# seccionamento.net
KiCad netlist of a schematic drawn in Altium Designer
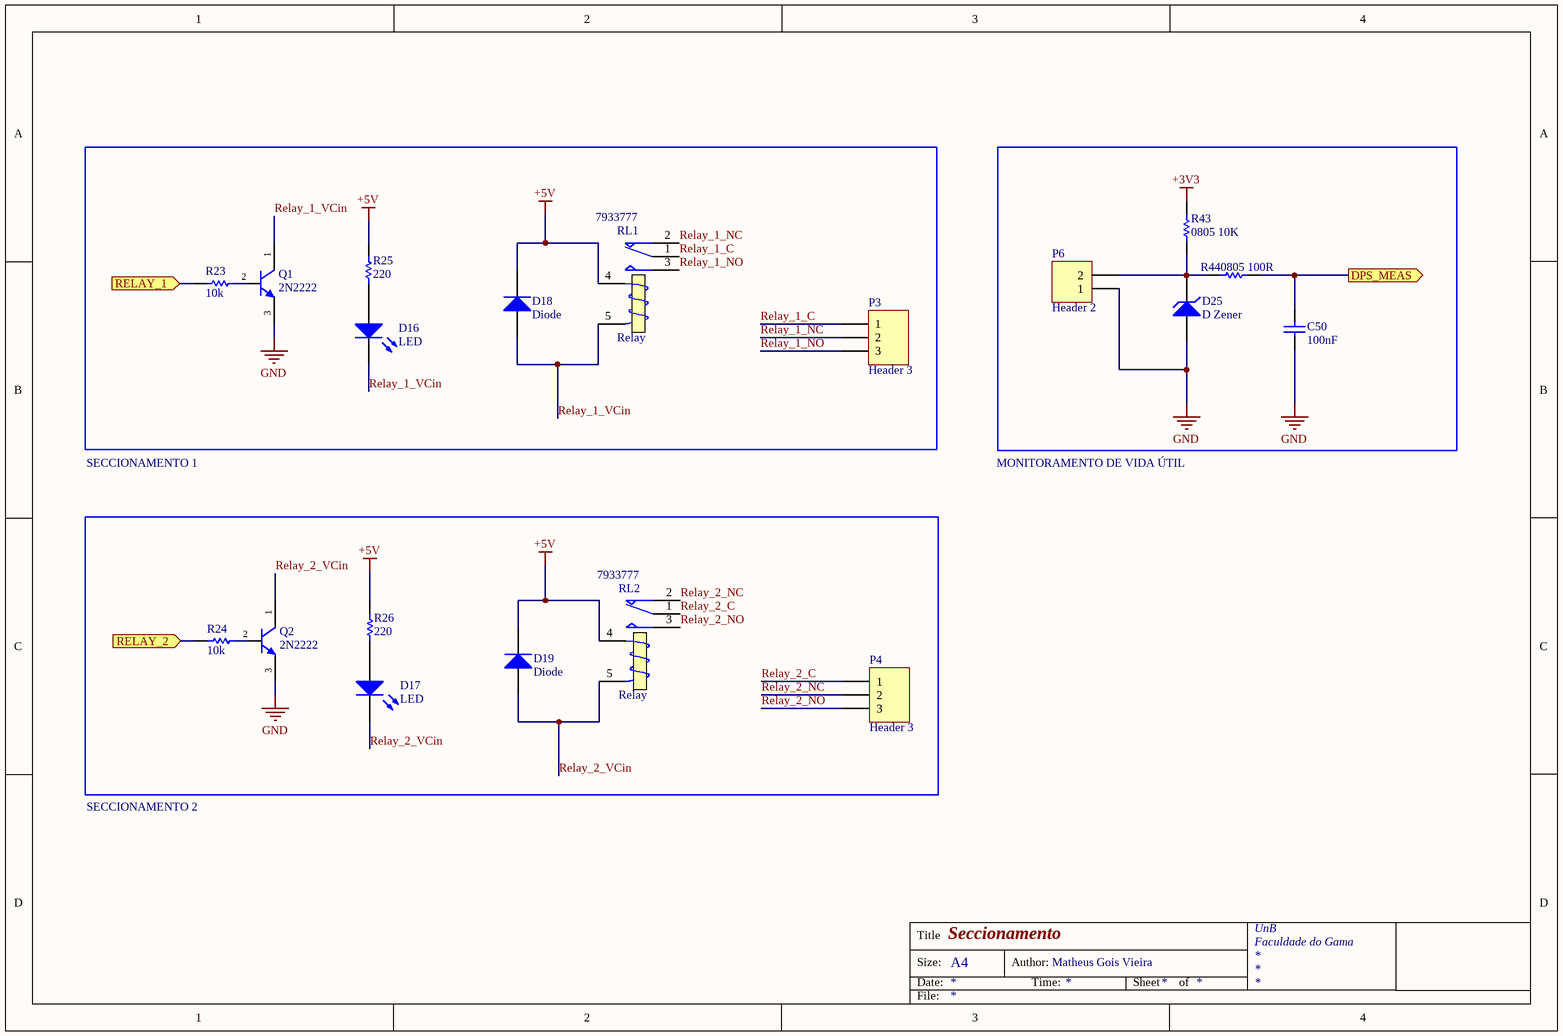
[diagram p0: seccionamento.SchDoc]

(export (version "E")
  (design (tool "Eeschema 10.0.6"))
  (components
    (comp (ref "C50")
      (value "100nF")
      (footprint "0603")
      (description "Capacitor Ceramic 100nF 20% 50V 0603 (1608 Metric) X7R")
      (fields (field (name "TOLERANCE") "20%") (field (name "MPN") "C0603C104M5RACTU"))
      (libsource (lib "Biblioteca_Clamper") (part "CAP CER SMD-0603 100nF - 50V"))
    )
    (comp (ref "D16")
      (value "LED")
      (footprint "LED-0603-G")
      (description "0603(H=0.9mm) 绿色 λD=569nm VR=5V VF=2.1V~2.6V IF=20mA PD=100mW")
      (fields (field (name "MANUFACTURER PART NUMBER") "LTST-C190GKT") (field (name "VOLTAGE") "2V"))
      (libsource (lib "Basic Library") (part "LED"))
    )
    (comp (ref "D17")
      (value "LED")
      (footprint "LED-0603-G")
      (description "0603(H=0.9mm) 绿色 λD=569nm VR=5V VF=2.1V~2.6V IF=20mA PD=100mW")
      (fields (field (name "MANUFACTURER PART NUMBER") "LTST-C190GKT") (field (name "VOLTAGE") "2V"))
      (libsource (lib "Basic Library") (part "LED"))
    )
    (comp (ref "D18")
      (value "Diode")
      (footprint "SMC")
      (description "VR=100V IF=200mA")
      (fields
        (field (name "MANUFACTURER") "ON Semiconductor / Fairchild")
        (field (name "MANUFACTURER PART NUMBER") "FDLL4148")
        (field (name "PUBLISHER") "Altium Limited")
      )
      (libsource (lib "Miscellaneous Devices") (part "Diode"))
    )
    (comp (ref "D19")
      (value "Diode")
      (footprint "SMC")
      (description "VR=100V IF=200mA")
      (fields
        (field (name "MANUFACTURER") "ON Semiconductor / Fairchild")
        (field (name "MANUFACTURER PART NUMBER") "FDLL4148")
        (field (name "PUBLISHER") "Altium Limited")
      )
      (libsource (lib "Miscellaneous Devices") (part "Diode"))
    )
    (comp (ref "D25")
      (value "D Zener")
      (footprint "DIODE-SIGNAL")
      (description "Diode Zener Single 9.1V 5% 500mW 2-Pin(1+Tab) Power Mite T/R")
      (fields (field (name "MANUFACTURER PART NUMBER") "1PMT5924BT1G") (field (name "TOLERANCE") "5%"))
      (libsource (lib "Basic Library") (part "D Zener"))
    )
    (comp (ref "P3")
      (value "Header 3")
      (footprint "HDR1X3")
      (description "Conn Terminal Block 3 POS 5mm Solder ST Thru-Hole 15A Bulk")
      (fields
        (field (name "MANUFACTURER") "Lumberg")
        (field (name "MANUFACTURER PART NUMBER") "KRESS03")
        (field (name "PUBLISHER") "Altium Limited")
      )
      (libsource (lib "Miscellaneous Connectors") (part "Header 3"))
    )
    (comp (ref "P4")
      (value "Header 3")
      (footprint "HDR1X3")
      (description "Conn Terminal Block 3 POS 5mm Solder ST Thru-Hole 15A Bulk")
      (fields
        (field (name "MANUFACTURER") "Lumberg")
        (field (name "MANUFACTURER PART NUMBER") "KRESS03")
        (field (name "PUBLISHER") "Altium Limited")
      )
      (libsource (lib "Miscellaneous Connectors") (part "Header 3"))
    )
    (comp (ref "P6")
      (value "Header 2")
      (footprint "HDR1X2")
      (description "间距5.08mm 2pin 母座 12A 320V 弯插 封边")
      (fields
        (field (name "MANUFACTURER") "Phoenix Contact")
        (field (name "MANUFACTURER PART NUMBER") "1757242")
        (field (name "PUBLISHER") "Altium Limited")
      )
      (libsource (lib "Miscellaneous Connectors") (part "Header 2"))
    )
    (comp (ref "Q1")
      (value "2N2222")
      (footprint "TO-220")
      (description "NPN Bipolar Transistor")
      (libsource (lib "Basic Library") (part "NPN"))
    )
    (comp (ref "Q2")
      (value "2N2222")
      (footprint "TO-220")
      (description "NPN Bipolar Transistor")
      (libsource (lib "Basic Library") (part "NPN"))
    )
    (comp (ref "R23")
      (value "10k")
      (footprint "R1608[0603]")
      (description "Res, 10K, 0.01%, 0.25W, 1206, Metal Foil")
      (fields (field (name "MANUFACTURER PART NUMBER") "Y163010K0000T9R") (field (name "TOLERANCE") "0.01%"))
      (libsource (lib "Basic Library") (part "R"))
    )
    (comp (ref "R24")
      (value "10k")
      (footprint "R1608[0603]")
      (description "Res, 10K, 0.01%, 0.25W, 1206, Metal Foil")
      (fields (field (name "MANUFACTURER PART NUMBER") "Y163010K0000T9R") (field (name "TOLERANCE") "0.01%"))
      (libsource (lib "Basic Library") (part "R"))
    )
    (comp (ref "R25")
      (value "220")
      (footprint "R1608[0603]")
      (description "Res Thick Film 0603 220 Ohm 1% 1/10W ±100ppm/°C Molded SMD Paper T/R")
      (fields (field (name "MANUFACTURER PART NUMBER") "Y163010K0000T9R") (field (name "TOLERANCE") "0.01%"))
      (libsource (lib "Basic Library") (part "R"))
    )
    (comp (ref "R26")
      (value "220")
      (footprint "R1608[0603]")
      (description "Res Thick Film 0603 220 Ohm 1% 1/10W ±100ppm/°C Molded SMD Paper T/R")
      (fields (field (name "MANUFACTURER PART NUMBER") "Y163010K0000T9R") (field (name "TOLERANCE") "0.01%"))
      (libsource (lib "Basic Library") (part "R"))
    )
    (comp (ref "R43")
      (value "0805 10K")
      (footprint "RES0805")
      (description "10K Omhs 0805 ± 1.00% 0.125W ± 100ppm/℃")
      (fields
        (field (name "MANUFACTURER") "Yageo")
        (field (name "MANUFACTURER PART NUMBER") "RC0603FR-0710KL")
      )
      (libsource (lib "occhi") (part "RC0805FR-0710KL"))
    )
    (comp (ref "R44")
      (value "0805 100R")
      (footprint "RES0805")
      (description "100R ± 1.00% 0.125W ± 100ppm/℃ 0805")
      (fields
        (field (name "MANUFACTURER") "Yageo")
        (field (name "MANUFACTURER PART NUMBER") "RC0805FR-07100RL")
      )
      (libsource (lib "occhi") (part "RC0805FR-07100RL"))
    )
    (comp (ref "RL1")
      (value "Relay")
      (footprint "FINDER-36.11")
      (description "SPDT PCB Mount Non-Latching Relay Through Hole; 12V dc")
      (fields
        (field (name "SUPPLIER PART NUMBER 1") "7933777")
        (field (name "MANUFACTURER PART NUMBER") "36.11.9.012.4011")
      )
      (libsource (lib "Basic Library") (part "Relay"))
    )
    (comp (ref "RL2")
      (value "Relay")
      (footprint "FINDER-36.11")
      (description "SPDT PCB Mount Non-Latching Relay Through Hole; 12V dc")
      (fields
        (field (name "SUPPLIER PART NUMBER 1") "7933777")
        (field (name "MANUFACTURER PART NUMBER") "36.11.9.012.4011")
      )
      (libsource (lib "Basic Library") (part "Relay"))
    )
  )
  (nets
    (net (code "1") (name "+3V3") (class "Default")
      (node (ref "R43") (pin "2") (pinfunction "2_2") (pintype "passive"))
    )
    (net (code "2") (name "+5V") (class "Default")
      (node (ref "D18") (pin "2") (pinfunction "K_2") (pintype "passive"))
      (node (ref "D19") (pin "2") (pinfunction "K_2") (pintype "passive"))
      (node (ref "R25") (pin "2") (pinfunction "2_2") (pintype "passive"))
      (node (ref "R26") (pin "2") (pinfunction "2_2") (pintype "passive"))
      (node (ref "RL1") (pin "4") (pinfunction "T1_4") (pintype "passive"))
      (node (ref "RL2") (pin "4") (pinfunction "T1_4") (pintype "passive"))
    )
    (net (code "3") (name "/DPS_MEAS") (class "Default")
      (node (ref "C50") (pin "1") (pinfunction "1_1") (pintype "passive"))
      (node (ref "R44") (pin "2") (pinfunction "2_2") (pintype "passive"))
    )
    (net (code "4") (name "/RELAY_1") (class "Default")
      (node (ref "R23") (pin "1") (pinfunction "1_1") (pintype "passive"))
    )
    (net (code "5") (name "/RELAY_2") (class "Default")
      (node (ref "R24") (pin "1") (pinfunction "1_1") (pintype "passive"))
    )
    (net (code "6") (name "/Relay_1_C") (class "Default")
      (node (ref "P3") (pin "1") (pinfunction "1_1") (pintype "passive"))
      (node (ref "RL1") (pin "1") (pinfunction "COM_1") (pintype "passive"))
    )
    (net (code "7") (name "/Relay_1_NC") (class "Default")
      (node (ref "P3") (pin "2") (pinfunction "2_2") (pintype "passive"))
      (node (ref "RL1") (pin "2") (pinfunction "NC_2") (pintype "passive"))
    )
    (net (code "8") (name "/Relay_1_NO") (class "Default")
      (node (ref "P3") (pin "3") (pinfunction "3_3") (pintype "passive"))
      (node (ref "RL1") (pin "3") (pinfunction "NO_3") (pintype "passive"))
    )
    (net (code "9") (name "/Relay_1_VCin") (class "Default")
      (node (ref "D16") (pin "2") (pinfunction "K_2") (pintype "passive"))
      (node (ref "D18") (pin "1") (pinfunction "A_1") (pintype "passive"))
      (node (ref "Q1") (pin "1") (pinfunction "C_1") (pintype "passive"))
      (node (ref "RL1") (pin "5") (pinfunction "T2_5") (pintype "passive"))
    )
    (net (code "10") (name "/Relay_2_C") (class "Default")
      (node (ref "P4") (pin "1") (pinfunction "1_1") (pintype "passive"))
      (node (ref "RL2") (pin "1") (pinfunction "COM_1") (pintype "passive"))
    )
    (net (code "11") (name "/Relay_2_NC") (class "Default")
      (node (ref "P4") (pin "2") (pinfunction "2_2") (pintype "passive"))
      (node (ref "RL2") (pin "2") (pinfunction "NC_2") (pintype "passive"))
    )
    (net (code "12") (name "/Relay_2_NO") (class "Default")
      (node (ref "P4") (pin "3") (pinfunction "3_3") (pintype "passive"))
      (node (ref "RL2") (pin "3") (pinfunction "NO_3") (pintype "passive"))
    )
    (net (code "13") (name "/Relay_2_VCin") (class "Default")
      (node (ref "D17") (pin "2") (pinfunction "K_2") (pintype "passive"))
      (node (ref "D19") (pin "1") (pinfunction "A_1") (pintype "passive"))
      (node (ref "Q2") (pin "1") (pinfunction "C_1") (pintype "passive"))
      (node (ref "RL2") (pin "5") (pinfunction "T2_5") (pintype "passive"))
    )
    (net (code "14") (name "GND") (class "Default")
      (node (ref "C50") (pin "2") (pinfunction "2_2") (pintype "passive"))
      (node (ref "D25") (pin "1") (pinfunction "A_1") (pintype "passive"))
      (node (ref "P6") (pin "1") (pinfunction "1_1") (pintype "passive"))
      (node (ref "Q1") (pin "3") (pinfunction "E_3") (pintype "passive"))
      (node (ref "Q2") (pin "3") (pinfunction "E_3") (pintype "passive"))
    )
    (net (code "15") (name "Net-(D16-A)") (class "Default")
      (node (ref "D16") (pin "1") (pinfunction "A_1") (pintype "passive"))
      (node (ref "R25") (pin "1") (pinfunction "1_1") (pintype "passive"))
    )
    (net (code "16") (name "Net-(D17-A)") (class "Default")
      (node (ref "D17") (pin "1") (pinfunction "A_1") (pintype "passive"))
      (node (ref "R26") (pin "1") (pinfunction "1_1") (pintype "passive"))
    )
    (net (code "17") (name "Net-(D25-K)") (class "Default")
      (node (ref "D25") (pin "2") (pinfunction "K_2") (pintype "passive"))
      (node (ref "P6") (pin "2") (pinfunction "2_2") (pintype "passive"))
      (node (ref "R43") (pin "1") (pinfunction "1_1") (pintype "passive"))
      (node (ref "R44") (pin "1") (pinfunction "1_1") (pintype "passive"))
    )
    (net (code "18") (name "Net-(Q1-B)") (class "Default")
      (node (ref "Q1") (pin "2") (pinfunction "B_2") (pintype "passive"))
      (node (ref "R23") (pin "2") (pinfunction "2_2") (pintype "passive"))
    )
    (net (code "19") (name "Net-(Q2-B)") (class "Default")
      (node (ref "Q2") (pin "2") (pinfunction "B_2") (pintype "passive"))
      (node (ref "R24") (pin "2") (pinfunction "2_2") (pintype "passive"))
    )
  )
)
